# ENGR301-project-Fall2023.net
KiCad netlist of a schematic drawn in EAGLE
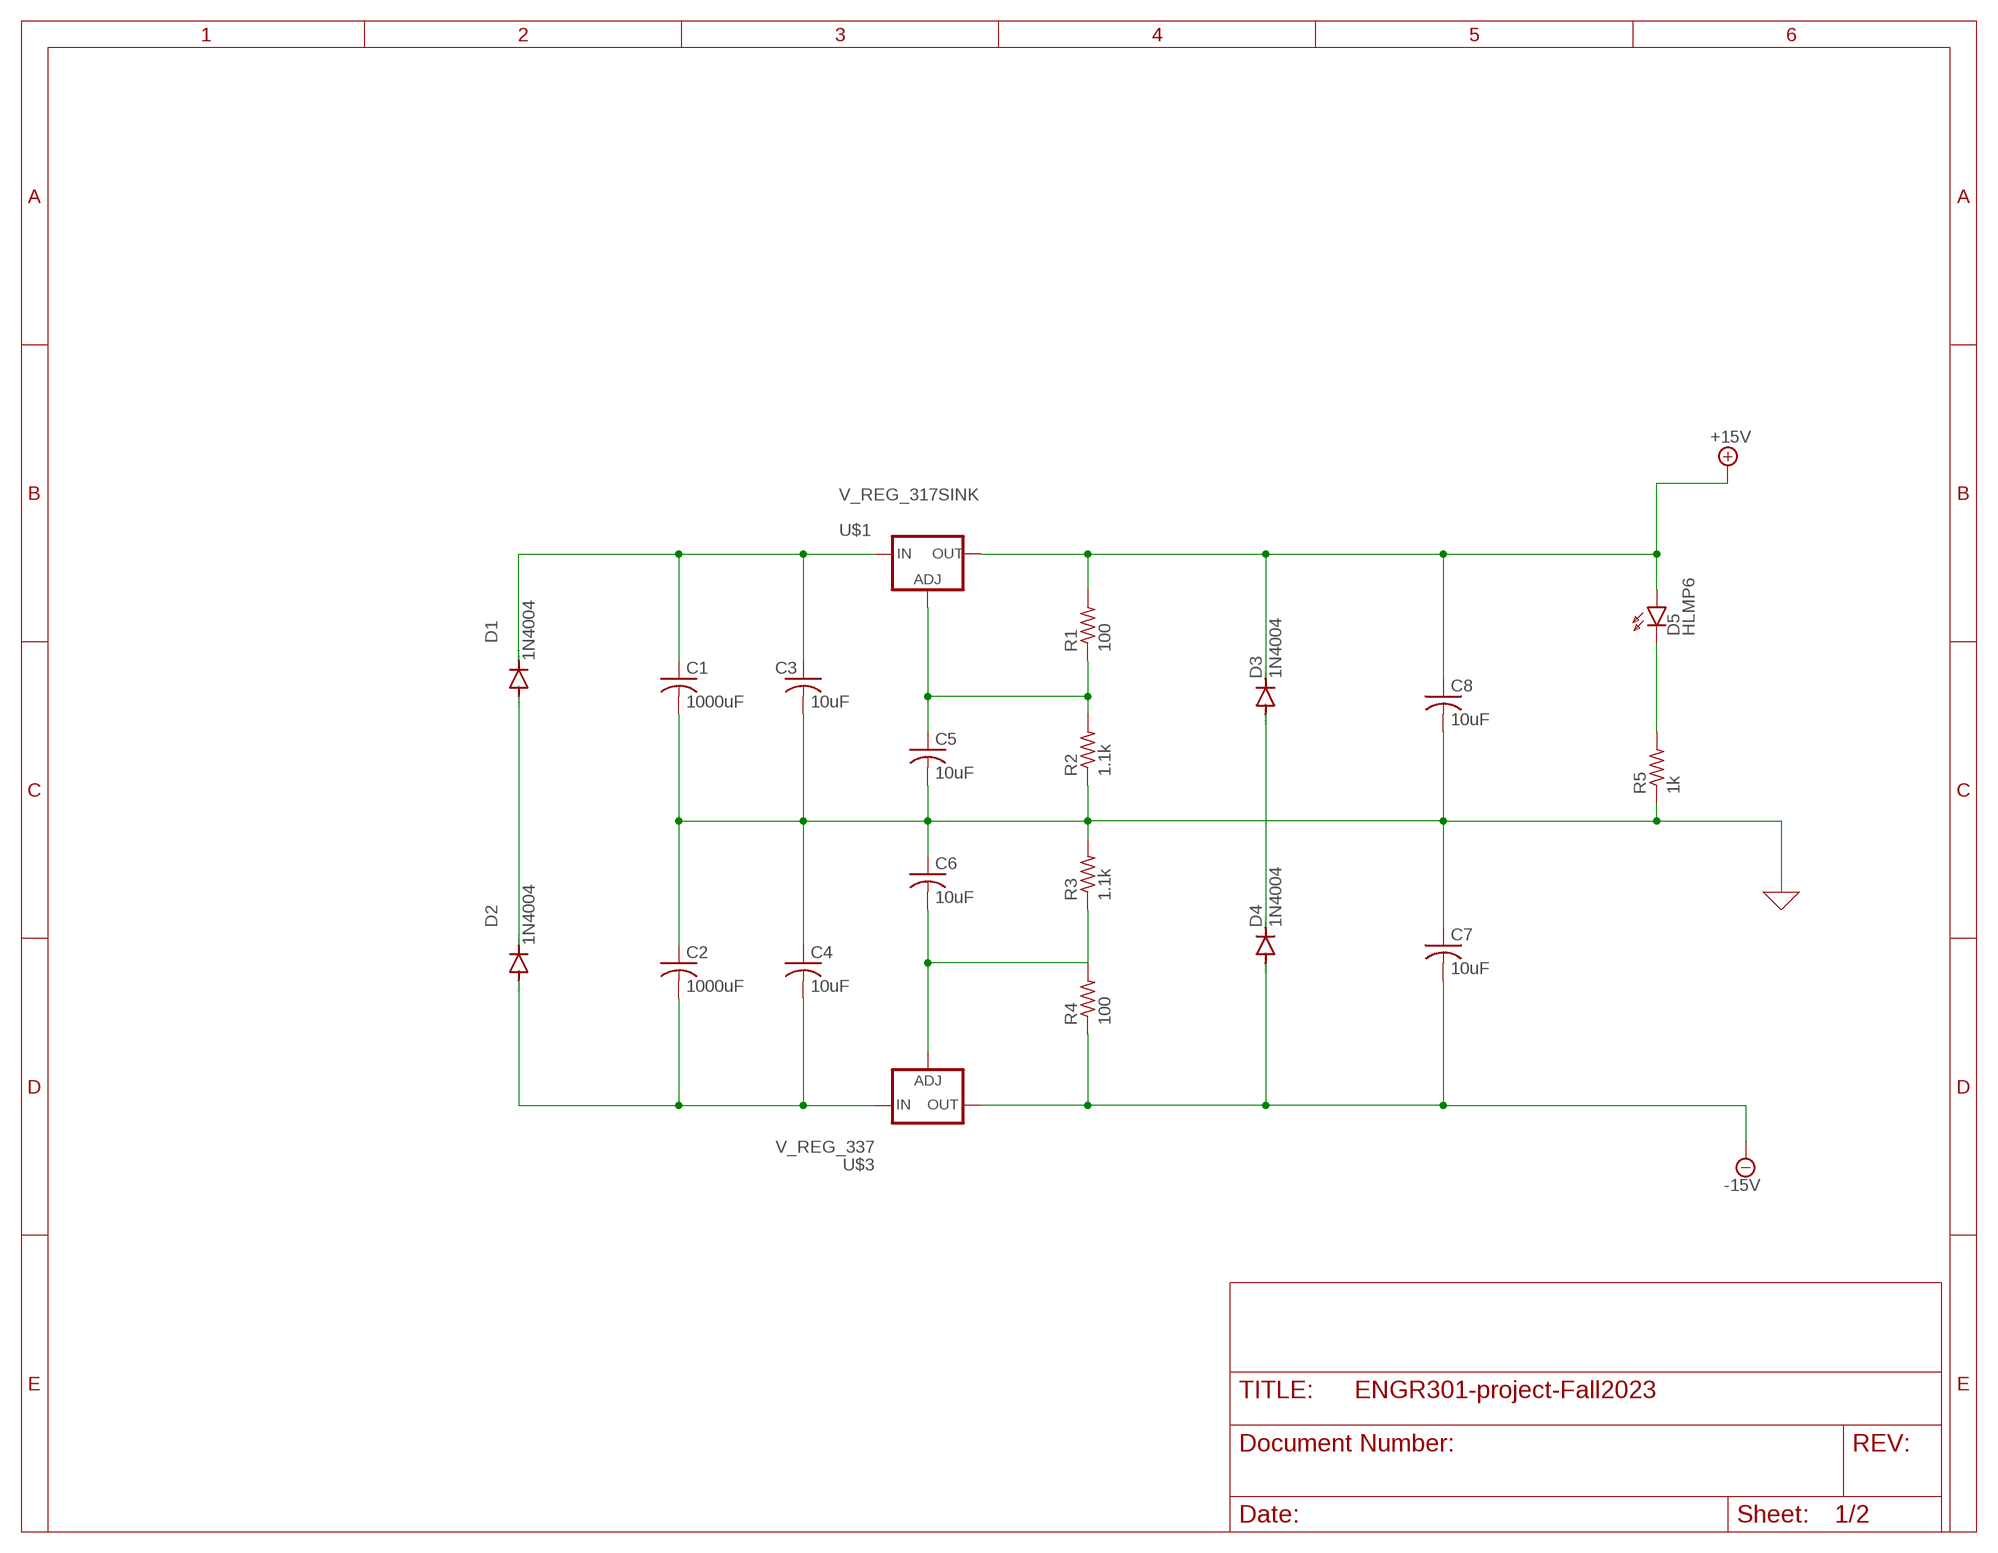
[diagram p0: schematic, sheet 1]
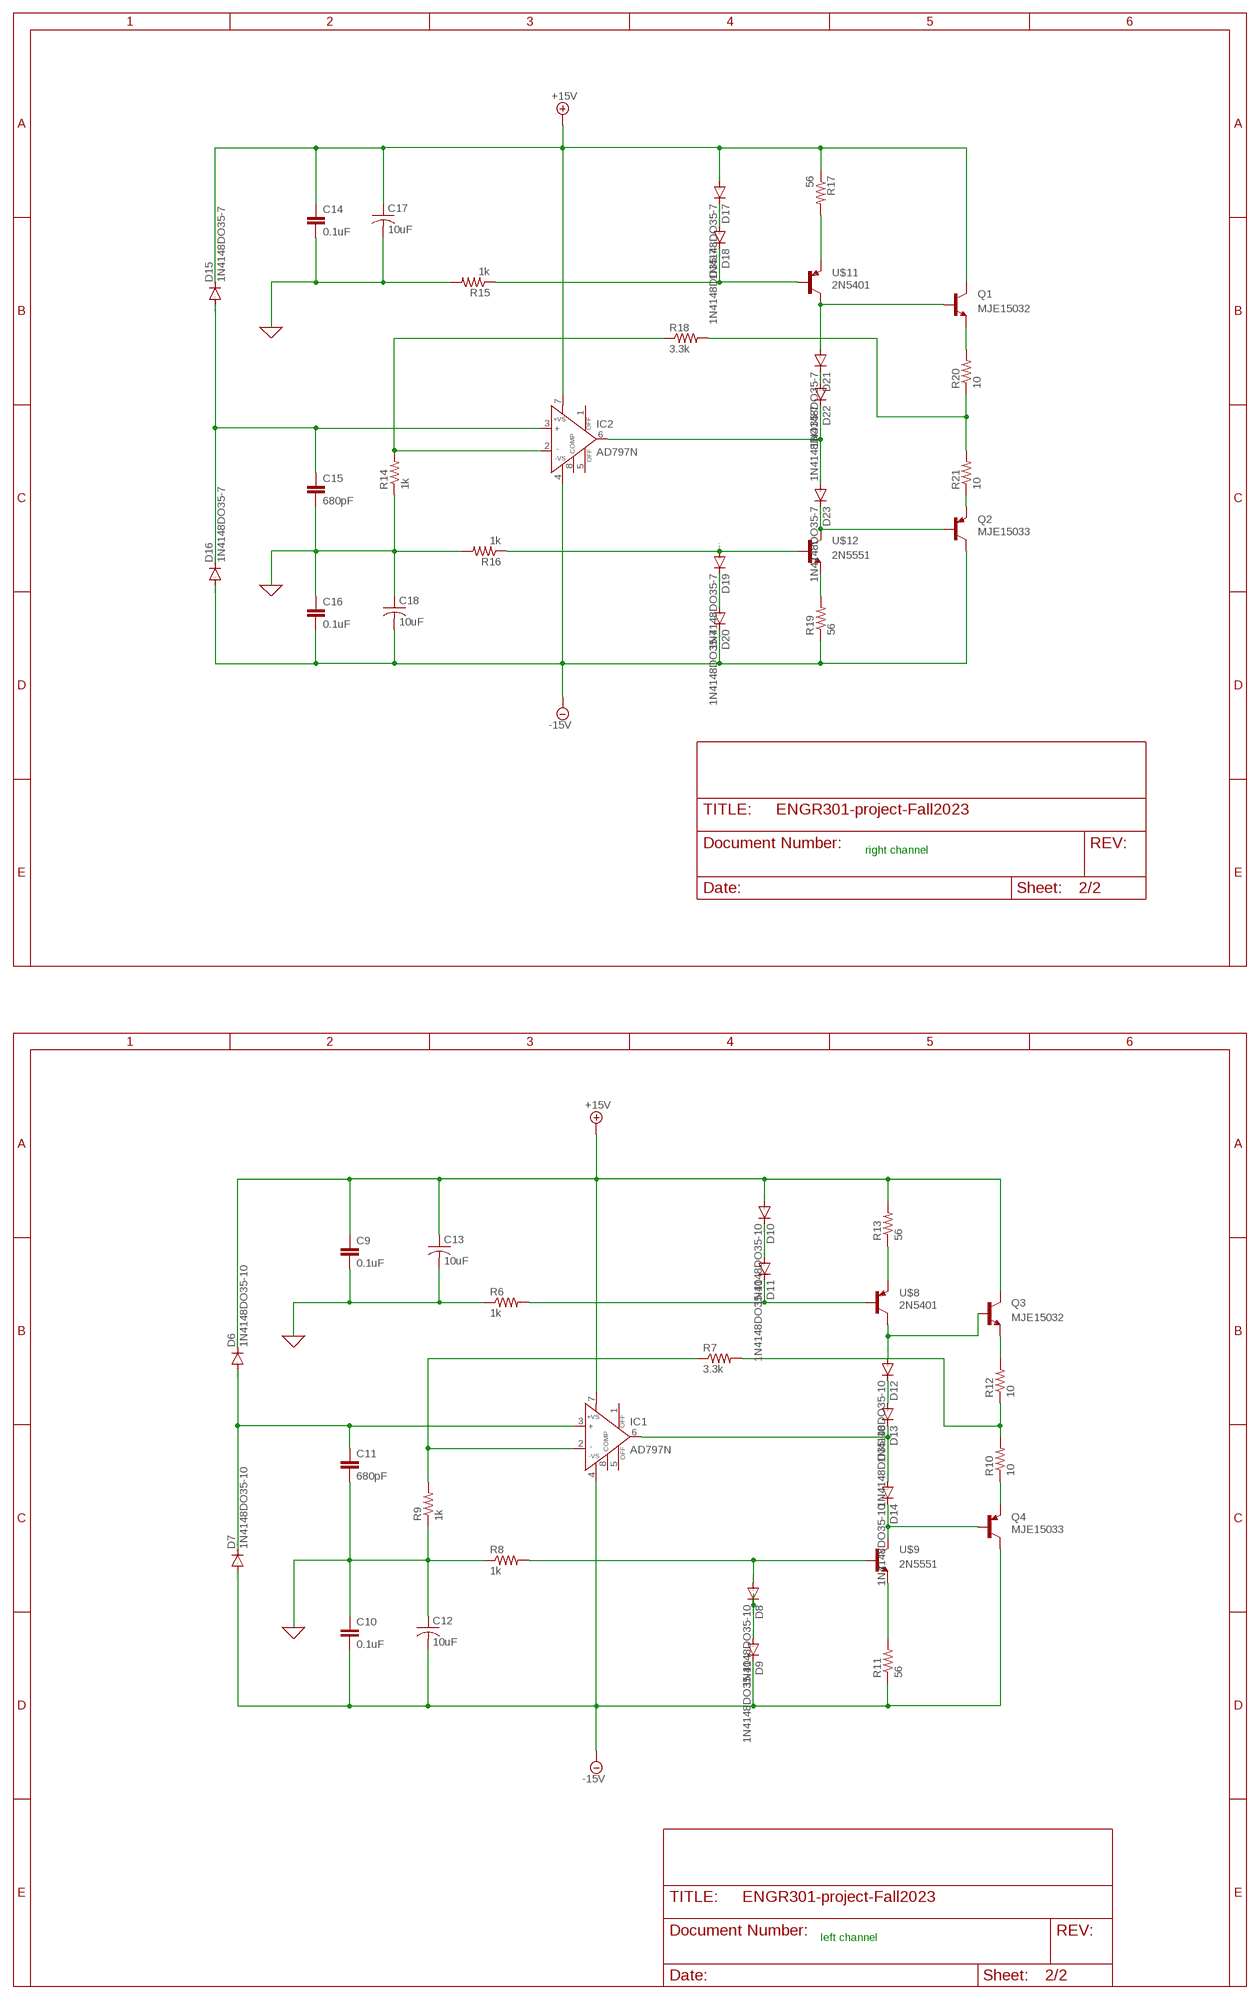
[diagram p1: schematic, sheet 2]

(export (version "E")
  (design (tool "Eeschema 10.0.6"))
  (components
    (comp (ref "C9")
      (value "0.1uF")
      (footprint "eagle-import:C2.5-3")
      (libsource (lib "eagle-import") (part "C2,5-3"))
    )
    (comp (ref "C10")
      (value "0.1uF")
      (footprint "eagle-import:C2.5-3")
      (libsource (lib "eagle-import") (part "C2,5-3"))
    )
    (comp (ref "C11")
      (value "680pF")
      (footprint "eagle-import:C2.5-3")
      (libsource (lib "eagle-import") (part "C2,5-3"))
    )
    (comp (ref "C12")
      (value "10uF")
      (footprint "eagle-import:C050-024X044")
      (libsource (lib "eagle-import") (part "C-US050-024X044"))
    )
    (comp (ref "C13")
      (value "10uF")
      (footprint "eagle-import:C050-024X044")
      (libsource (lib "eagle-import") (part "C-US050-024X044"))
    )
    (comp (ref "C14")
      (value "0.1uF")
      (footprint "eagle-import:C2.5-3")
      (libsource (lib "eagle-import") (part "C2,5-3"))
    )
    (comp (ref "C15")
      (value "680pF")
      (footprint "eagle-import:C2.5-3")
      (libsource (lib "eagle-import") (part "C2,5-3"))
    )
    (comp (ref "C16")
      (value "0.1uF")
      (footprint "eagle-import:C2.5-3")
      (libsource (lib "eagle-import") (part "C2,5-3"))
    )
    (comp (ref "C17")
      (value "10uF")
      (footprint "eagle-import:C050-024X044")
      (libsource (lib "eagle-import") (part "C-US050-024X044"))
    )
    (comp (ref "C18")
      (value "10uF")
      (footprint "eagle-import:C050-024X044")
      (libsource (lib "eagle-import") (part "C-US050-024X044"))
    )
    (comp (ref "D6")
      (value "1N4148DO35-10")
      (footprint "eagle-import:DO35-10")
      (libsource (lib "eagle-import") (part "1N4148DO35-10"))
    )
    (comp (ref "D7")
      (value "1N4148DO35-10")
      (footprint "eagle-import:DO35-10")
      (libsource (lib "eagle-import") (part "1N4148DO35-10"))
    )
    (comp (ref "D8")
      (value "1N4148DO35-10")
      (footprint "eagle-import:DO35-10")
      (libsource (lib "eagle-import") (part "1N4148DO35-10"))
    )
    (comp (ref "D9")
      (value "1N4148DO35-10")
      (footprint "eagle-import:DO35-10")
      (libsource (lib "eagle-import") (part "1N4148DO35-10"))
    )
    (comp (ref "D10")
      (value "1N4148DO35-10")
      (footprint "eagle-import:DO35-10")
      (libsource (lib "eagle-import") (part "1N4148DO35-10"))
    )
    (comp (ref "D11")
      (value "1N4148DO35-10")
      (footprint "eagle-import:DO35-10")
      (libsource (lib "eagle-import") (part "1N4148DO35-10"))
    )
    (comp (ref "D12")
      (value "1N4148DO35-10")
      (footprint "eagle-import:DO35-10")
      (libsource (lib "eagle-import") (part "1N4148DO35-10"))
    )
    (comp (ref "D13")
      (value "1N4148DO35-10")
      (footprint "eagle-import:DO35-10")
      (libsource (lib "eagle-import") (part "1N4148DO35-10"))
    )
    (comp (ref "D14")
      (value "1N4148DO35-10")
      (footprint "eagle-import:DO35-10")
      (libsource (lib "eagle-import") (part "1N4148DO35-10"))
    )
    (comp (ref "D15")
      (value "1N4148DO35-7")
      (footprint "eagle-import:DO35-7")
      (libsource (lib "eagle-import") (part "1N4148DO35-7"))
    )
    (comp (ref "D16")
      (value "1N4148DO35-7")
      (footprint "eagle-import:DO35-7")
      (libsource (lib "eagle-import") (part "1N4148DO35-7"))
    )
    (comp (ref "D17")
      (value "1N4148DO35-7")
      (footprint "eagle-import:DO35-7")
      (libsource (lib "eagle-import") (part "1N4148DO35-7"))
    )
    (comp (ref "D18")
      (value "1N4148DO35-7")
      (footprint "eagle-import:DO35-7")
      (libsource (lib "eagle-import") (part "1N4148DO35-7"))
    )
    (comp (ref "D19")
      (value "1N4148DO35-7")
      (footprint "eagle-import:DO35-7")
      (libsource (lib "eagle-import") (part "1N4148DO35-7"))
    )
    (comp (ref "D20")
      (value "1N4148DO35-7")
      (footprint "eagle-import:DO35-7")
      (libsource (lib "eagle-import") (part "1N4148DO35-7"))
    )
    (comp (ref "D21")
      (value "1N4148DO35-7")
      (footprint "eagle-import:DO35-7")
      (libsource (lib "eagle-import") (part "1N4148DO35-7"))
    )
    (comp (ref "D22")
      (value "1N4148DO35-7")
      (footprint "eagle-import:DO35-7")
      (libsource (lib "eagle-import") (part "1N4148DO35-7"))
    )
    (comp (ref "D23")
      (value "1N4148DO35-7")
      (footprint "eagle-import:DO35-7")
      (libsource (lib "eagle-import") (part "1N4148DO35-7"))
    )
    (comp (ref "IC1")
      (value "AD797N")
      (footprint "eagle-import:DIL08")
      (fields (field (name "MF") "ALTERA CORPORATION") (field (name "MPN") "AD797ANZ"))
      (libsource (lib "eagle-import") (part "AD797N"))
    )
    (comp (ref "IC2")
      (value "AD797N")
      (footprint "eagle-import:DIL08")
      (fields (field (name "MF") "ALTERA CORPORATION") (field (name "MPN") "AD797ANZ"))
      (libsource (lib "eagle-import") (part "AD797N"))
    )
    (comp (ref "Q1")
      (value "MJE15032")
      (footprint "eagle-import:TO220V")
      (libsource (lib "eagle-import") (part "MJE15032"))
    )
    (comp (ref "Q2")
      (value "MJE15033")
      (footprint "eagle-import:TO220V")
      (libsource (lib "eagle-import") (part "MJE15033"))
    )
    (comp (ref "Q3")
      (value "MJE15032")
      (footprint "eagle-import:TO220V")
      (libsource (lib "eagle-import") (part "MJE15032"))
    )
    (comp (ref "Q4")
      (value "MJE15033")
      (footprint "eagle-import:TO220V")
      (libsource (lib "eagle-import") (part "MJE15033"))
    )
    (comp (ref "R6")
      (value "1k")
      (footprint "eagle-import:0204_7")
      (libsource (lib "eagle-import") (part "R-US_0204/7"))
    )
    (comp (ref "R7")
      (value "3.3k")
      (footprint "eagle-import:0204_7")
      (libsource (lib "eagle-import") (part "R-US_0204/7"))
    )
    (comp (ref "R8")
      (value "1k")
      (footprint "eagle-import:0204_7")
      (libsource (lib "eagle-import") (part "R-US_0204/7"))
    )
    (comp (ref "R9")
      (value "1k")
      (footprint "eagle-import:0204_7")
      (libsource (lib "eagle-import") (part "R-US_0204/7"))
    )
    (comp (ref "R10")
      (value "10")
      (footprint "eagle-import:0204_7")
      (libsource (lib "eagle-import") (part "R-US_0204/7"))
    )
    (comp (ref "R11")
      (value "56")
      (footprint "eagle-import:0204_7")
      (libsource (lib "eagle-import") (part "R-US_0204/7"))
    )
    (comp (ref "R12")
      (value "10")
      (footprint "eagle-import:0204_7")
      (libsource (lib "eagle-import") (part "R-US_0204/7"))
    )
    (comp (ref "R13")
      (value "56")
      (footprint "eagle-import:0204_7")
      (libsource (lib "eagle-import") (part "R-US_0204/7"))
    )
    (comp (ref "R14")
      (value "1k")
      (footprint "eagle-import:0204_7")
      (libsource (lib "eagle-import") (part "R-US_0204/7"))
    )
    (comp (ref "R15")
      (value "1k")
      (footprint "eagle-import:0204_7")
      (libsource (lib "eagle-import") (part "R-US_0204/7"))
    )
    (comp (ref "R16")
      (value "1k")
      (footprint "eagle-import:0204_7")
      (libsource (lib "eagle-import") (part "R-US_0204/7"))
    )
    (comp (ref "R17")
      (value "56")
      (footprint "eagle-import:0204_7")
      (libsource (lib "eagle-import") (part "R-US_0204/7"))
    )
    (comp (ref "R18")
      (value "3.3k")
      (footprint "eagle-import:0204_7")
      (libsource (lib "eagle-import") (part "R-US_0204/7"))
    )
    (comp (ref "R19")
      (value "56")
      (footprint "eagle-import:0204_7")
      (libsource (lib "eagle-import") (part "R-US_0204/7"))
    )
    (comp (ref "R20")
      (value "10")
      (footprint "eagle-import:0204_7")
      (libsource (lib "eagle-import") (part "R-US_0204/7"))
    )
    (comp (ref "R21")
      (value "10")
      (footprint "eagle-import:0204_7")
      (libsource (lib "eagle-import") (part "R-US_0204/7"))
    )
    (comp (ref "U$8")
      (value "2N5401")
      (footprint "eagle-import:2N5401")
      (libsource (lib "eagle-import") (part "2N5401"))
    )
    (comp (ref "U$9")
      (value "2N5551")
      (footprint "eagle-import:2N5551")
      (libsource (lib "eagle-import") (part "2N5551"))
    )
    (comp (ref "U$11")
      (value "2N5401")
      (footprint "eagle-import:2N5401")
      (libsource (lib "eagle-import") (part "2N5401"))
    )
    (comp (ref "U$12")
      (value "2N5551")
      (footprint "eagle-import:2N5551")
      (libsource (lib "eagle-import") (part "2N5551"))
    )
    (comp (ref "C1")
      (value "1000uF")
      (footprint "eagle-import:C050-024X044")
      (libsource (lib "eagle-import") (part "C-US050-024X044"))
    )
    (comp (ref "C2")
      (value "1000uF")
      (footprint "eagle-import:C050-024X044")
      (libsource (lib "eagle-import") (part "C-US050-024X044"))
    )
    (comp (ref "C3")
      (value "10uF")
      (footprint "eagle-import:C050-024X044")
      (libsource (lib "eagle-import") (part "C-US050-024X044"))
    )
    (comp (ref "C4")
      (value "10uF")
      (footprint "eagle-import:C050-024X044")
      (libsource (lib "eagle-import") (part "C-US050-024X044"))
    )
    (comp (ref "C5")
      (value "10uF")
      (footprint "eagle-import:C050-024X044")
      (libsource (lib "eagle-import") (part "C-US050-024X044"))
    )
    (comp (ref "C6")
      (value "10uF")
      (footprint "eagle-import:C050-024X044")
      (libsource (lib "eagle-import") (part "C-US050-024X044"))
    )
    (comp (ref "C7")
      (value "10uF")
      (footprint "eagle-import:C050-024X044")
      (libsource (lib "eagle-import") (part "C-US050-024X044"))
    )
    (comp (ref "C8")
      (value "10uF")
      (footprint "eagle-import:C050-024X044")
      (libsource (lib "eagle-import") (part "C-US050-024X044"))
    )
    (comp (ref "D1")
      (value "1N4004")
      (footprint "eagle-import:DO41-10")
      (libsource (lib "eagle-import") (part "1N4004"))
    )
    (comp (ref "D2")
      (value "1N4004")
      (footprint "eagle-import:DO41-10")
      (libsource (lib "eagle-import") (part "1N4004"))
    )
    (comp (ref "D3")
      (value "1N4004")
      (footprint "eagle-import:DO41-10")
      (libsource (lib "eagle-import") (part "1N4004"))
    )
    (comp (ref "D4")
      (value "1N4004")
      (footprint "eagle-import:DO41-10")
      (libsource (lib "eagle-import") (part "1N4004"))
    )
    (comp (ref "D5")
      (value "HLMP6")
      (footprint "eagle-import:HLMP6")
      (fields (field (name "MF") "AGILENT TECHNOLOGIES") (field (name "MPN") "HLMP-6500"))
      (libsource (lib "eagle-import") (part "HLMP6"))
    )
    (comp (ref "R1")
      (value "100")
      (footprint "eagle-import:0204_7")
      (libsource (lib "eagle-import") (part "R-US_0204/7"))
    )
    (comp (ref "R2")
      (value "1.1k")
      (footprint "eagle-import:0204_7")
      (libsource (lib "eagle-import") (part "R-US_0204/7"))
    )
    (comp (ref "R3")
      (value "1.1k")
      (footprint "eagle-import:0204_7")
      (libsource (lib "eagle-import") (part "R-US_0204/7"))
    )
    (comp (ref "R4")
      (value "100")
      (footprint "eagle-import:0204_7")
      (libsource (lib "eagle-import") (part "R-US_0204/7"))
    )
    (comp (ref "R5")
      (value "1k")
      (footprint "eagle-import:0204_7")
      (libsource (lib "eagle-import") (part "R-US_0204/7"))
    )
    (comp (ref "U$1")
      (value "V_REG_317SINK")
      (footprint "eagle-import:TO220-ADJ")
      (libsource (lib "eagle-import") (part "V_REG_317SINK"))
    )
    (comp (ref "U$3")
      (value "V_REG_337")
      (footprint "eagle-import:TO220-ADJ-NEG")
      (libsource (lib "eagle-import") (part "V_REG_337"))
    )
  )
  (nets
    (net (code "1") (name "+15V") (class "Default")
      (node (ref "C13") (pin "1") (pinfunction "1_1") (pintype "passive"))
      (node (ref "C14") (pin "1") (pinfunction "1_1") (pintype "passive"))
      (node (ref "C17") (pin "1") (pinfunction "1_1") (pintype "passive"))
      (node (ref "C8") (pin "1") (pinfunction "1_1") (pintype "passive"))
      (node (ref "C9") (pin "1") (pinfunction "1_1") (pintype "passive"))
      (node (ref "D10") (pin "A") (pinfunction "A_A") (pintype "passive"))
      (node (ref "D15") (pin "C") (pinfunction "C_C") (pintype "passive"))
      (node (ref "D17") (pin "A") (pinfunction "A_A") (pintype "passive"))
      (node (ref "D3") (pin "C") (pinfunction "C_C") (pintype "passive"))
      (node (ref "D5") (pin "A") (pinfunction "A_A") (pintype "passive"))
      (node (ref "D6") (pin "C") (pinfunction "C_C") (pintype "passive"))
      (node (ref "IC1") (pin "7") (pinfunction "+VS_7") (pintype "input"))
      (node (ref "IC2") (pin "7") (pinfunction "+VS_7") (pintype "input"))
      (node (ref "Q1") (pin "2") (pinfunction "C_2") (pintype "passive"))
      (node (ref "Q3") (pin "2") (pinfunction "C_2") (pintype "passive"))
      (node (ref "R1") (pin "2") (pinfunction "2_2") (pintype "passive"))
      (node (ref "R13") (pin "2") (pinfunction "2_2") (pintype "passive"))
      (node (ref "R17") (pin "1") (pinfunction "1_1") (pintype "passive"))
      (node (ref "U$1") (pin "OUT") (pinfunction "OUT_OUT") (pintype "output"))
    )
    (net (code "2") (name "-15V") (class "Default")
      (node (ref "C10") (pin "2") (pinfunction "2_2") (pintype "passive"))
      (node (ref "C12") (pin "2") (pinfunction "2_2") (pintype "passive"))
      (node (ref "C16") (pin "2") (pinfunction "2_2") (pintype "passive"))
      (node (ref "C18") (pin "2") (pinfunction "2_2") (pintype "passive"))
      (node (ref "C7") (pin "2") (pinfunction "2_2") (pintype "passive"))
      (node (ref "D16") (pin "A") (pinfunction "A_A") (pintype "passive"))
      (node (ref "D20") (pin "C") (pinfunction "C_C") (pintype "passive"))
      (node (ref "D4") (pin "A") (pinfunction "A_A") (pintype "passive"))
      (node (ref "D7") (pin "A") (pinfunction "A_A") (pintype "passive"))
      (node (ref "D9") (pin "C") (pinfunction "C_C") (pintype "passive"))
      (node (ref "IC1") (pin "4") (pinfunction "-VS_4") (pintype "input"))
      (node (ref "IC2") (pin "4") (pinfunction "-VS_4") (pintype "input"))
      (node (ref "Q2") (pin "2") (pinfunction "C_2") (pintype "passive"))
      (node (ref "Q4") (pin "2") (pinfunction "C_2") (pintype "passive"))
      (node (ref "R11") (pin "1") (pinfunction "1_1") (pintype "passive"))
      (node (ref "R19") (pin "1") (pinfunction "1_1") (pintype "passive"))
      (node (ref "R4") (pin "1") (pinfunction "1_1") (pintype "passive"))
      (node (ref "U$3") (pin "OUT") (pinfunction "OUT_OUT") (pintype "output"))
    )
    (net (code "3") (name "0") (class "Default")
      (node (ref "C1") (pin "2") (pinfunction "2_2") (pintype "passive"))
      (node (ref "C10") (pin "1") (pinfunction "1_1") (pintype "passive"))
      (node (ref "C11") (pin "2") (pinfunction "2_2") (pintype "passive"))
      (node (ref "C12") (pin "1") (pinfunction "1_1") (pintype "passive"))
      (node (ref "C13") (pin "2") (pinfunction "2_2") (pintype "passive"))
      (node (ref "C14") (pin "2") (pinfunction "2_2") (pintype "passive"))
      (node (ref "C15") (pin "2") (pinfunction "2_2") (pintype "passive"))
      (node (ref "C16") (pin "1") (pinfunction "1_1") (pintype "passive"))
      (node (ref "C17") (pin "2") (pinfunction "2_2") (pintype "passive"))
      (node (ref "C18") (pin "1") (pinfunction "1_1") (pintype "passive"))
      (node (ref "C2") (pin "1") (pinfunction "1_1") (pintype "passive"))
      (node (ref "C3") (pin "2") (pinfunction "2_2") (pintype "passive"))
      (node (ref "C4") (pin "1") (pinfunction "1_1") (pintype "passive"))
      (node (ref "C5") (pin "2") (pinfunction "2_2") (pintype "passive"))
      (node (ref "C6") (pin "1") (pinfunction "1_1") (pintype "passive"))
      (node (ref "C7") (pin "1") (pinfunction "1_1") (pintype "passive"))
      (node (ref "C8") (pin "2") (pinfunction "2_2") (pintype "passive"))
      (node (ref "C9") (pin "2") (pinfunction "2_2") (pintype "passive"))
      (node (ref "R14") (pin "1") (pinfunction "1_1") (pintype "passive"))
      (node (ref "R15") (pin "2") (pinfunction "2_2") (pintype "passive"))
      (node (ref "R16") (pin "2") (pinfunction "2_2") (pintype "passive"))
      (node (ref "R2") (pin "1") (pinfunction "1_1") (pintype "passive"))
      (node (ref "R3") (pin "2") (pinfunction "2_2") (pintype "passive"))
      (node (ref "R5") (pin "1") (pinfunction "1_1") (pintype "passive"))
      (node (ref "R6") (pin "1") (pinfunction "1_1") (pintype "passive"))
      (node (ref "R8") (pin "1") (pinfunction "1_1") (pintype "passive"))
      (node (ref "R9") (pin "1") (pinfunction "1_1") (pintype "passive"))
    )
    (net (code "4") (name "Net-(C1-Pad1)") (class "Default")
      (node (ref "C1") (pin "1") (pinfunction "1_1") (pintype "passive"))
      (node (ref "C3") (pin "1") (pinfunction "1_1") (pintype "passive"))
      (node (ref "D1") (pin "C") (pinfunction "C_C") (pintype "passive"))
      (node (ref "U$1") (pin "IN") (pinfunction "IN_IN") (pintype "input"))
    )
    (net (code "5") (name "Net-(C2-Pad2)") (class "Default")
      (node (ref "C2") (pin "2") (pinfunction "2_2") (pintype "passive"))
      (node (ref "C4") (pin "2") (pinfunction "2_2") (pintype "passive"))
      (node (ref "D2") (pin "A") (pinfunction "A_A") (pintype "passive"))
      (node (ref "U$3") (pin "IN") (pinfunction "IN_IN") (pintype "input"))
    )
    (net (code "6") (name "Net-(C5-Pad1)") (class "Default")
      (node (ref "C5") (pin "1") (pinfunction "1_1") (pintype "passive"))
      (node (ref "R1") (pin "1") (pinfunction "1_1") (pintype "passive"))
      (node (ref "R2") (pin "2") (pinfunction "2_2") (pintype "passive"))
      (node (ref "U$1") (pin "ADJ") (pinfunction "ADJ_ADJ") (pintype "input"))
    )
    (net (code "7") (name "Net-(C6-Pad2)") (class "Default")
      (node (ref "C6") (pin "2") (pinfunction "2_2") (pintype "passive"))
      (node (ref "R3") (pin "1") (pinfunction "1_1") (pintype "passive"))
      (node (ref "R4") (pin "2") (pinfunction "2_2") (pintype "passive"))
      (node (ref "U$3") (pin "ADJ") (pinfunction "ADJ_ADJ") (pintype "input"))
    )
    (net (code "8") (name "Net-(D1-PadA)") (class "Default")
      (node (ref "D1") (pin "A") (pinfunction "A_A") (pintype "passive"))
      (node (ref "D2") (pin "C") (pinfunction "C_C") (pintype "passive"))
    )
    (net (code "9") (name "Net-(D3-PadA)") (class "Default")
      (node (ref "D3") (pin "A") (pinfunction "A_A") (pintype "passive"))
      (node (ref "D4") (pin "C") (pinfunction "C_C") (pintype "passive"))
    )
    (net (code "10") (name "Net-(D5-PadK)") (class "Default")
      (node (ref "D5") (pin "K") (pinfunction "K_K") (pintype "passive"))
      (node (ref "R5") (pin "2") (pinfunction "2_2") (pintype "passive"))
    )
    (net (code "11") (name "Net-(D8-PadA)") (class "Default")
      (node (ref "D8") (pin "A") (pinfunction "A_A") (pintype "passive"))
      (node (ref "R8") (pin "2") (pinfunction "2_2") (pintype "passive"))
      (node (ref "U$9") (pin "B") (pinfunction "B_B") (pintype "passive"))
    )
    (net (code "12") (name "Net-(D8-PadC)") (class "Default")
      (node (ref "D8") (pin "C") (pinfunction "C_C") (pintype "passive"))
      (node (ref "D9") (pin "A") (pinfunction "A_A") (pintype "passive"))
    )
    (net (code "13") (name "Net-(D10-PadC)") (class "Default")
      (node (ref "D10") (pin "C") (pinfunction "C_C") (pintype "passive"))
      (node (ref "D11") (pin "A") (pinfunction "A_A") (pintype "passive"))
    )
    (net (code "14") (name "Net-(D11-PadC)") (class "Default")
      (node (ref "D11") (pin "C") (pinfunction "C_C") (pintype "passive"))
      (node (ref "R6") (pin "2") (pinfunction "2_2") (pintype "passive"))
      (node (ref "U$8") (pin "B") (pinfunction "B_B") (pintype "passive"))
    )
    (net (code "15") (name "Net-(D12-PadC)") (class "Default")
      (node (ref "D12") (pin "C") (pinfunction "C_C") (pintype "passive"))
      (node (ref "D13") (pin "A") (pinfunction "A_A") (pintype "passive"))
    )
    (net (code "16") (name "Net-(D17-PadC)") (class "Default")
      (node (ref "D17") (pin "C") (pinfunction "C_C") (pintype "passive"))
      (node (ref "D18") (pin "A") (pinfunction "A_A") (pintype "passive"))
    )
    (net (code "17") (name "Net-(D18-PadC)") (class "Default")
      (node (ref "D18") (pin "C") (pinfunction "C_C") (pintype "passive"))
      (node (ref "R15") (pin "1") (pinfunction "1_1") (pintype "passive"))
      (node (ref "U$11") (pin "B") (pinfunction "B_B") (pintype "passive"))
    )
    (net (code "18") (name "Net-(D19-PadA)") (class "Default")
      (node (ref "D19") (pin "A") (pinfunction "A_A") (pintype "passive"))
      (node (ref "R16") (pin "1") (pinfunction "1_1") (pintype "passive"))
      (node (ref "U$12") (pin "B") (pinfunction "B_B") (pintype "passive"))
    )
    (net (code "19") (name "Net-(D19-PadC)") (class "Default")
      (node (ref "D19") (pin "C") (pinfunction "C_C") (pintype "passive"))
      (node (ref "D20") (pin "A") (pinfunction "A_A") (pintype "passive"))
    )
    (net (code "20") (name "Net-(D21-PadC)") (class "Default")
      (node (ref "D21") (pin "C") (pinfunction "C_C") (pintype "passive"))
      (node (ref "D22") (pin "A") (pinfunction "A_A") (pintype "passive"))
    )
    (net (code "21") (name "Net-(IC1-IN+)") (class "Default")
      (node (ref "C11") (pin "1") (pinfunction "1_1") (pintype "passive"))
      (node (ref "D6") (pin "A") (pinfunction "A_A") (pintype "passive"))
      (node (ref "D7") (pin "C") (pinfunction "C_C") (pintype "passive"))
      (node (ref "IC1") (pin "3") (pinfunction "IN+_3") (pintype "input"))
    )
    (net (code "22") (name "Net-(IC1-IN-)") (class "Default")
      (node (ref "IC1") (pin "2") (pinfunction "IN-_2") (pintype "input"))
      (node (ref "R7") (pin "1") (pinfunction "1_1") (pintype "passive"))
      (node (ref "R9") (pin "2") (pinfunction "2_2") (pintype "passive"))
    )
    (net (code "23") (name "Net-(IC1-OUT)") (class "Default")
      (node (ref "D13") (pin "C") (pinfunction "C_C") (pintype "passive"))
      (node (ref "D14") (pin "A") (pinfunction "A_A") (pintype "passive"))
      (node (ref "IC1") (pin "6") (pinfunction "OUT_6") (pintype "output"))
    )
    (net (code "24") (name "Net-(IC2-IN+)") (class "Default")
      (node (ref "C15") (pin "1") (pinfunction "1_1") (pintype "passive"))
      (node (ref "D15") (pin "A") (pinfunction "A_A") (pintype "passive"))
      (node (ref "D16") (pin "C") (pinfunction "C_C") (pintype "passive"))
      (node (ref "IC2") (pin "3") (pinfunction "IN+_3") (pintype "input"))
    )
    (net (code "25") (name "Net-(IC2-IN-)") (class "Default")
      (node (ref "IC2") (pin "2") (pinfunction "IN-_2") (pintype "input"))
      (node (ref "R14") (pin "2") (pinfunction "2_2") (pintype "passive"))
      (node (ref "R18") (pin "1") (pinfunction "1_1") (pintype "passive"))
    )
    (net (code "26") (name "Net-(IC2-OUT)") (class "Default")
      (node (ref "D22") (pin "C") (pinfunction "C_C") (pintype "passive"))
      (node (ref "D23") (pin "A") (pinfunction "A_A") (pintype "passive"))
      (node (ref "IC2") (pin "6") (pinfunction "OUT_6") (pintype "output"))
    )
    (net (code "27") (name "Net-(Q1-B)") (class "Default")
      (node (ref "D21") (pin "A") (pinfunction "A_A") (pintype "passive"))
      (node (ref "Q1") (pin "1") (pinfunction "B_1") (pintype "passive"))
      (node (ref "U$11") (pin "E") (pinfunction "C_E") (pintype "passive"))
    )
    (net (code "28") (name "Net-(Q1-E)") (class "Default")
      (node (ref "Q1") (pin "3") (pinfunction "E_3") (pintype "passive"))
      (node (ref "R20") (pin "2") (pinfunction "2_2") (pintype "passive"))
    )
    (net (code "29") (name "Net-(Q2-B)") (class "Default")
      (node (ref "D23") (pin "C") (pinfunction "C_C") (pintype "passive"))
      (node (ref "Q2") (pin "1") (pinfunction "B_1") (pintype "passive"))
      (node (ref "U$12") (pin "C") (pinfunction "C_C") (pintype "passive"))
    )
    (net (code "30") (name "Net-(Q2-E)") (class "Default")
      (node (ref "Q2") (pin "3") (pinfunction "E_3") (pintype "passive"))
      (node (ref "R21") (pin "1") (pinfunction "1_1") (pintype "passive"))
    )
    (net (code "31") (name "Net-(Q3-B)") (class "Default")
      (node (ref "D12") (pin "A") (pinfunction "A_A") (pintype "passive"))
      (node (ref "Q3") (pin "1") (pinfunction "B_1") (pintype "passive"))
      (node (ref "U$8") (pin "E") (pinfunction "C_E") (pintype "passive"))
    )
    (net (code "32") (name "Net-(Q3-E)") (class "Default")
      (node (ref "Q3") (pin "3") (pinfunction "E_3") (pintype "passive"))
      (node (ref "R12") (pin "2") (pinfunction "2_2") (pintype "passive"))
    )
    (net (code "33") (name "Net-(Q4-B)") (class "Default")
      (node (ref "D14") (pin "C") (pinfunction "C_C") (pintype "passive"))
      (node (ref "Q4") (pin "1") (pinfunction "B_1") (pintype "passive"))
      (node (ref "U$9") (pin "C") (pinfunction "C_C") (pintype "passive"))
    )
    (net (code "34") (name "Net-(Q4-E)") (class "Default")
      (node (ref "Q4") (pin "3") (pinfunction "E_3") (pintype "passive"))
      (node (ref "R10") (pin "1") (pinfunction "1_1") (pintype "passive"))
    )
    (net (code "35") (name "Net-(R10-Pad2)") (class "Default")
      (node (ref "R10") (pin "2") (pinfunction "2_2") (pintype "passive"))
      (node (ref "R12") (pin "1") (pinfunction "1_1") (pintype "passive"))
      (node (ref "R7") (pin "2") (pinfunction "2_2") (pintype "passive"))
    )
    (net (code "36") (name "Net-(R11-Pad2)") (class "Default")
      (node (ref "R11") (pin "2") (pinfunction "2_2") (pintype "passive"))
      (node (ref "U$9") (pin "E") (pinfunction "E_E") (pintype "passive"))
    )
    (net (code "37") (name "Net-(R18-Pad2)") (class "Default")
      (node (ref "R18") (pin "2") (pinfunction "2_2") (pintype "passive"))
      (node (ref "R20") (pin "1") (pinfunction "1_1") (pintype "passive"))
      (node (ref "R21") (pin "2") (pinfunction "2_2") (pintype "passive"))
    )
    (net (code "38") (name "Net-(R19-Pad2)") (class "Default")
      (node (ref "R19") (pin "2") (pinfunction "2_2") (pintype "passive"))
      (node (ref "U$12") (pin "E") (pinfunction "E_E") (pintype "passive"))
    )
    (net (code "39") (name "Net-(U$8-E)") (class "Default")
      (node (ref "R13") (pin "1") (pinfunction "1_1") (pintype "passive"))
      (node (ref "U$8") (pin "C") (pinfunction "E_C") (pintype "passive"))
    )
    (net (code "40") (name "Net-(U$11-E)") (class "Default")
      (node (ref "R17") (pin "2") (pinfunction "2_2") (pintype "passive"))
      (node (ref "U$11") (pin "C") (pinfunction "E_C") (pintype "passive"))
    )
    (net (code "41") (name "unconnected-(IC1-COMP-Pad8)") (class "Default")
      (node (ref "IC1") (pin "8") (pinfunction "COMP_8") (pintype "passive"))
    )
    (net (code "42") (name "unconnected-(IC1-OFF-Pad1)") (class "Default")
      (node (ref "IC1") (pin "1") (pinfunction "OFF_1") (pintype "passive"))
    )
    (net (code "43") (name "unconnected-(IC1-OFF-Pad5)") (class "Default")
      (node (ref "IC1") (pin "5") (pinfunction "OFF_5") (pintype "passive"))
    )
    (net (code "44") (name "unconnected-(IC2-COMP-Pad8)") (class "Default")
      (node (ref "IC2") (pin "8") (pinfunction "COMP_8") (pintype "passive"))
    )
    (net (code "45") (name "unconnected-(IC2-OFF-Pad1)") (class "Default")
      (node (ref "IC2") (pin "1") (pinfunction "OFF_1") (pintype "passive"))
    )
    (net (code "46") (name "unconnected-(IC2-OFF-Pad5)") (class "Default")
      (node (ref "IC2") (pin "5") (pinfunction "OFF_5") (pintype "passive"))
    )
  )
)
